# LAN9252-1.net
KiCad netlist of a schematic drawn in Altium Designer
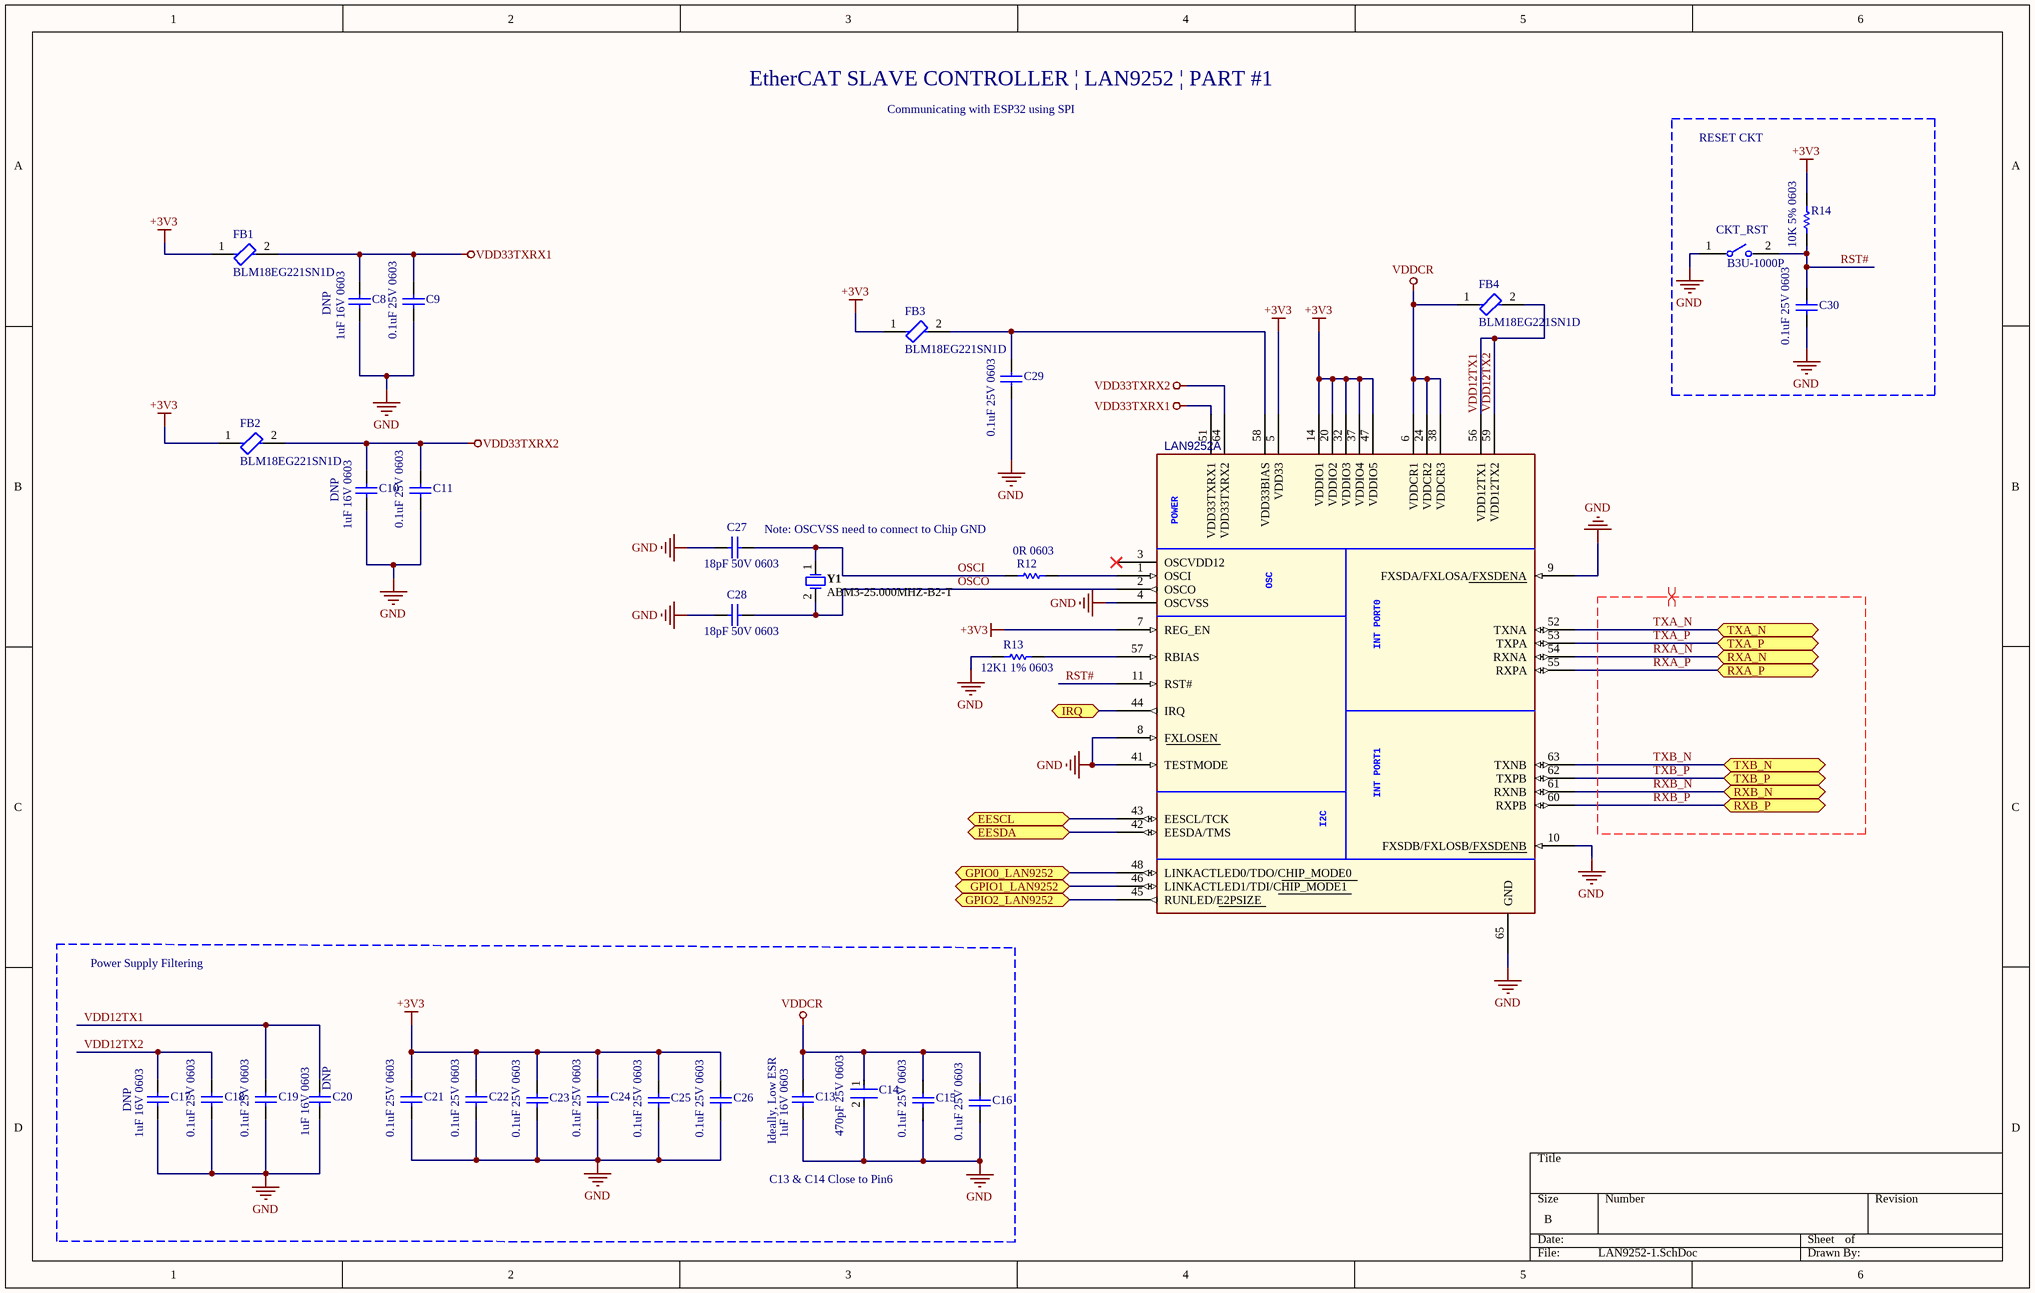
[diagram p0: LAN9252-1.SchDoc]

(export (version "E")
  (design (tool "Eeschema 10.0.6"))
  (components
    (comp (ref "C8")
      (value "1uF 16V 0603")
      (footprint "CAPC1608X90X35LL15T15")
      (fields (field (name "MANUFACTURER") "Kemet") (field (name "PART NUMBER") "C0603C105K4RACTU"))
      (libsource (lib "Altium Content Vault") (part "CAP"))
    )
    (comp (ref "C9")
      (value "0.1uF 25V 0603")
      (footprint "CAPC1608X90X35LL10T15")
      (fields (field (name "PART NUMBER") "GRM188R71E104KA01D") (field (name "MANUFACTURER") "Murata"))
      (libsource (lib "Altium Content Vault") (part "CAP"))
    )
    (comp (ref "C10")
      (value "1uF 16V 0603")
      (footprint "CAPC1608X90X35LL15T15")
      (fields (field (name "MANUFACTURER") "Kemet") (field (name "PART NUMBER") "C0603C105K4RACTU"))
      (libsource (lib "Altium Content Vault") (part "CAP"))
    )
    (comp (ref "C11")
      (value "0.1uF 25V 0603")
      (footprint "CAPC1608X90X35LL10T15")
      (fields (field (name "PART NUMBER") "GRM188R71E104KA01D") (field (name "MANUFACTURER") "Murata"))
      (libsource (lib "Altium Content Vault") (part "CAP"))
    )
    (comp (ref "C13")
      (value "1uF 16V 0603")
      (footprint "CAPC1608X90X35LL15T15")
      (fields (field (name "MANUFACTURER") "Kemet") (field (name "PART NUMBER") "C0603C105K4RACTU"))
      (libsource (lib "Altium Content Vault") (part "CAP"))
    )
    (comp (ref "C14")
      (value "470pF 25V 0603")
      (footprint "FP-C0603C-CF-MFG")
      (description "CAP CER 470PF 25V 10% X7R 0603")
      (fields (field (name "MANUFACTURER") "KEMET") (field (name "TOLERANCE") "0.1"))
      (libsource (lib "Altium Content Vault") (part "b4654b650e69147ec39a6b967a45e02"))
    )
    (comp (ref "C15")
      (value "0.1uF 25V 0603")
      (footprint "CAPC1608X90X35LL10T15")
      (fields (field (name "PART NUMBER") "GRM188R71E104KA01D") (field (name "MANUFACTURER") "Murata"))
      (libsource (lib "Altium Content Vault") (part "CAP"))
    )
    (comp (ref "C16")
      (value "0.1uF 25V 0603")
      (footprint "CAPC1608X90X35LL10T15")
      (fields (field (name "PART NUMBER") "GRM188R71E104KA01D") (field (name "MANUFACTURER") "Murata"))
      (libsource (lib "Altium Content Vault") (part "CAP"))
    )
    (comp (ref "C17")
      (value "1uF 16V 0603")
      (footprint "CAPC1608X90X35LL15T15")
      (fields (field (name "MANUFACTURER") "Kemet") (field (name "PART NUMBER") "C0603C105K4RACTU"))
      (libsource (lib "Altium Content Vault") (part "CAP"))
    )
    (comp (ref "C18")
      (value "0.1uF 25V 0603")
      (footprint "CAPC1608X90X35LL10T15")
      (fields (field (name "PART NUMBER") "GRM188R71E104KA01D") (field (name "MANUFACTURER") "Murata"))
      (libsource (lib "Altium Content Vault") (part "CAP"))
    )
    (comp (ref "C19")
      (value "0.1uF 25V 0603")
      (footprint "CAPC1608X90X35LL10T15")
      (fields (field (name "PART NUMBER") "GRM188R71E104KA01D") (field (name "MANUFACTURER") "Murata"))
      (libsource (lib "Altium Content Vault") (part "CAP"))
    )
    (comp (ref "C20")
      (value "1uF 16V 0603")
      (footprint "CAPC1608X90X35LL15T15")
      (fields (field (name "MANUFACTURER") "Kemet") (field (name "PART NUMBER") "C0603C105K4RACTU"))
      (libsource (lib "Altium Content Vault") (part "CAP"))
    )
    (comp (ref "C21")
      (value "0.1uF 25V 0603")
      (footprint "CAPC1608X90X35LL10T15")
      (fields (field (name "PART NUMBER") "GRM188R71E104KA01D") (field (name "MANUFACTURER") "Murata"))
      (libsource (lib "Altium Content Vault") (part "CAP"))
    )
    (comp (ref "C22")
      (value "0.1uF 25V 0603")
      (footprint "CAPC1608X90X35LL10T15")
      (fields (field (name "PART NUMBER") "GRM188R71E104KA01D") (field (name "MANUFACTURER") "Murata"))
      (libsource (lib "Altium Content Vault") (part "CAP"))
    )
    (comp (ref "C23")
      (value "0.1uF 25V 0603")
      (footprint "CAPC1608X90X35LL10T15")
      (fields (field (name "PART NUMBER") "GRM188R71E104KA01D") (field (name "MANUFACTURER") "Murata"))
      (libsource (lib "Altium Content Vault") (part "CAP"))
    )
    (comp (ref "C24")
      (value "0.1uF 25V 0603")
      (footprint "CAPC1608X90X35LL10T15")
      (fields (field (name "PART NUMBER") "GRM188R71E104KA01D") (field (name "MANUFACTURER") "Murata"))
      (libsource (lib "Altium Content Vault") (part "CAP"))
    )
    (comp (ref "C25")
      (value "0.1uF 25V 0603")
      (footprint "CAPC1608X90X35LL10T15")
      (fields (field (name "PART NUMBER") "GRM188R71E104KA01D") (field (name "MANUFACTURER") "Murata"))
      (libsource (lib "Altium Content Vault") (part "CAP"))
    )
    (comp (ref "C26")
      (value "0.1uF 25V 0603")
      (footprint "CAPC1608X90X35LL10T15")
      (fields (field (name "PART NUMBER") "GRM188R71E104KA01D") (field (name "MANUFACTURER") "Murata"))
      (libsource (lib "Altium Content Vault") (part "CAP"))
    )
    (comp (ref "C27")
      (value "18pF 50V 0603")
      (footprint "CAPC1608X90X40LL10T20")
      (description "Chip Capacitor, 18 pF, +/- 5%, 50 V, -55 to 125 degC, 0603 (1608 Metric), RoHS, Tape and Reel")
      (fields (field (name "TOLERANCE") "1%"))
      (libsource (lib "Altium Content Vault") (part "CAP-NP-2"))
    )
    (comp (ref "C28")
      (value "18pF 50V 0603")
      (footprint "CAPC1608X90X40LL10T20")
      (description "Chip Capacitor, 18 pF, +/- 5%, 50 V, -55 to 125 degC, 0603 (1608 Metric), RoHS, Tape and Reel")
      (fields (field (name "TOLERANCE") "1%"))
      (libsource (lib "Altium Content Vault") (part "CAP-NP-2"))
    )
    (comp (ref "C29")
      (value "0.1uF 25V 0603")
      (footprint "CAPC1608X90X35LL10T15")
      (fields (field (name "PART NUMBER") "GRM188R71E104KA01D") (field (name "MANUFACTURER") "Murata"))
      (libsource (lib "Altium Content Vault") (part "CAP"))
    )
    (comp (ref "C30")
      (value "0.1uF 25V 0603")
      (footprint "CAPC1608X90X35LL10T15")
      (fields (field (name "PART NUMBER") "GRM188R71E104KA01D") (field (name "MANUFACTURER") "Murata"))
      (libsource (lib "Altium Content Vault") (part "CAP"))
    )
    (comp (ref "CKT_RST")
      (value "B3U-1000P")
      (footprint "FP-B3U-1000P-MFG")
      (description "SWITCH TACTILE SPST-NO 0.05A 12V")
      (libsource (lib "Altium Content Vault") (part "ae622034201233ca1abcedc05908f33"))
    )
    (comp (ref "FB1")
      (value "BLM18EG221SN1D")
      (footprint "FP-BLM18-0_15-t0_8-MFG")
      (description "Chip Ferrite Bead, 0603, 220Ω @ 100MHz, 0.05Ω, 25%, 2A")
      (fields (field (name "TOLERANCE") "25%"))
      (libsource (lib "Altium Content Vault") (part "5f30dd21d616792df468990f7003faa"))
    )
    (comp (ref "FB2")
      (value "BLM18EG221SN1D")
      (footprint "FP-BLM18-0_15-t0_8-MFG")
      (description "Chip Ferrite Bead, 0603, 220Ω @ 100MHz, 0.05Ω, 25%, 2A")
      (fields (field (name "TOLERANCE") "25%"))
      (libsource (lib "Altium Content Vault") (part "5f30dd21d616792df468990f7003faa"))
    )
    (comp (ref "FB3")
      (value "BLM18EG221SN1D")
      (footprint "FP-BLM18-0_15-t0_8-MFG")
      (description "Chip Ferrite Bead, 0603, 220Ω @ 100MHz, 0.05Ω, 25%, 2A")
      (fields (field (name "TOLERANCE") "25%"))
      (libsource (lib "Altium Content Vault") (part "5f30dd21d616792df468990f7003faa"))
    )
    (comp (ref "FB4")
      (value "BLM18EG221SN1D")
      (footprint "FP-BLM18-0_15-t0_8-MFG")
      (description "Chip Ferrite Bead, 0603, 220Ω @ 100MHz, 0.05Ω, 25%, 2A")
      (fields (field (name "TOLERANCE") "25%"))
      (libsource (lib "Altium Content Vault") (part "5f30dd21d616792df468990f7003faa"))
    )
    (comp (ref "LAN9252")
      (value "~")
      (footprint "LAN9252_QFN")
      (description "IC, 2/3-Port EtherCAT® Slave Controller, QFN64")
      (fields (field (name "OWNER") "Manikandan"))
      (libsource (lib "UNG_UNG") (part "LAN9252_QFN64"))
    )
    (comp (ref "R12")
      (value "0R 0603")
      (footprint "RESC1608X55X25ML10T15")
      (description "Chip Resistor, 0 Ohm, +/- 5%, 0.1 W, -55 to 155 degC, 0603 (1608 Metric), RoHS, Tape and Reel")
      (fields (field (name "TOLERANCE") "5%") (field (name "MANUFACTURER") "Yageo"))
      (libsource (lib "Altium Content Vault") (part "RES-2"))
    )
    (comp (ref "R13")
      (value "12K1 1% 0603")
      (footprint "RESC0603X28X15ML05T05")
      (fields (field (name "PART NUMBER") "CRCW020112K1FNED") (field (name "MANUFACTURER") "Vishay Dale"))
      (libsource (lib "Altium Content Vault") (part "RES"))
    )
    (comp (ref "R14")
      (value "10K 5% 0603")
      (footprint "RESC1608X55X25ML10T15")
      (description "Chip Resistor, 10 KOhm, +/- 1%, 01 W, -55 to 155 degC, 0603 (1608 Metric), RoHS, Tape and Reel")
      (fields (field (name "MANUFACTURER") "Yageo") (field (name "TOLERANCE") "1%"))
      (libsource (lib "Altium Content Vault") (part "RES-2"))
    )
    (comp (ref "Y1")
      (value "ABM3-25.000MHZ-B2-T")
      (footprint "ABRA-ABM3_V")
      (description "Miniature Ceramic Crystal, 25 MHz, +/- 20 ppm, -20 to 70 degC, 2-Pin SMD, RoHS, Tape and Reel")
      (fields (field (name "TOLERANCE") "20PPM") (field (name "MANUFACTURER") "ABRACON"))
      (libsource (lib "Altium Content Vault") (part "XTAL-1-2-2"))
    )
  )
  (nets
    (net (code "1") (name "+3V3") (class "Default")
      (node (ref "C21") (pin "2") (pinfunction "2_2") (pintype "passive"))
      (node (ref "C22") (pin "2") (pinfunction "2_2") (pintype "passive"))
      (node (ref "C23") (pin "2") (pinfunction "2_2") (pintype "passive"))
      (node (ref "C24") (pin "2") (pinfunction "2_2") (pintype "passive"))
      (node (ref "C25") (pin "2") (pinfunction "2_2") (pintype "passive"))
      (node (ref "C26") (pin "2") (pinfunction "2_2") (pintype "passive"))
      (node (ref "FB1") (pin "1") (pinfunction "1_1") (pintype "passive"))
      (node (ref "FB2") (pin "1") (pinfunction "1_1") (pintype "passive"))
      (node (ref "FB3") (pin "1") (pinfunction "1_1") (pintype "passive"))
      (node (ref "LAN9252") (pin "14") (pinfunction "VDDIO1_14") (pintype "power_in"))
      (node (ref "LAN9252") (pin "20") (pinfunction "VDDIO2_20") (pintype "power_in"))
      (node (ref "LAN9252") (pin "32") (pinfunction "VDDIO3_32") (pintype "power_in"))
      (node (ref "LAN9252") (pin "37") (pinfunction "VDDIO4_37") (pintype "power_in"))
      (node (ref "LAN9252") (pin "47") (pinfunction "VDDIO5_47") (pintype "power_in"))
      (node (ref "LAN9252") (pin "5") (pinfunction "VDD33_5") (pintype "power_in"))
      (node (ref "LAN9252") (pin "7") (pinfunction "REG_EN_7") (pintype "input"))
      (node (ref "R14") (pin "2") (pinfunction "2_2") (pintype "passive"))
    )
    (net (code "2") (name "/EESCL") (class "Default")
      (node (ref "LAN9252") (pin "43") (pinfunction "EESCL/TCK_43") (pintype "bidirectional"))
    )
    (net (code "3") (name "/EESDA") (class "Default")
      (node (ref "LAN9252") (pin "42") (pinfunction "EESDA/TMS_42") (pintype "bidirectional"))
    )
    (net (code "4") (name "/GPIO0_LAN9252") (class "Default")
      (node (ref "LAN9252") (pin "48") (pinfunction "LINKACTLED0/TDO/CHIP_MODE0_48") (pintype "bidirectional"))
    )
    (net (code "5") (name "/GPIO1_LAN9252") (class "Default")
      (node (ref "LAN9252") (pin "46") (pinfunction "LINKACTLED1/TDI/CHIP_MODE1_46") (pintype "bidirectional"))
    )
    (net (code "6") (name "/GPIO2_LAN9252") (class "Default")
      (node (ref "LAN9252") (pin "45") (pinfunction "RUNLED/E2PSIZE_45") (pintype "output"))
    )
    (net (code "7") (name "/IRQ") (class "Default")
      (node (ref "LAN9252") (pin "44") (pinfunction "IRQ_44") (pintype "output"))
    )
    (net (code "8") (name "/OSCI") (class "Default")
      (node (ref "C27") (pin "2") (pinfunction "2_2") (pintype "passive"))
      (node (ref "R12") (pin "1") (pinfunction "1_1") (pintype "passive"))
      (node (ref "Y1") (pin "1") (pinfunction "1_1") (pintype "passive"))
    )
    (net (code "9") (name "/OSCO") (class "Default")
      (node (ref "C28") (pin "2") (pinfunction "2_2") (pintype "passive"))
      (node (ref "LAN9252") (pin "2") (pinfunction "OSCO_2") (pintype "output"))
      (node (ref "Y1") (pin "2") (pinfunction "2_2") (pintype "passive"))
    )
    (net (code "10") (name "/RST#") (class "Default")
      (node (ref "C30") (pin "2") (pinfunction "2_2") (pintype "passive"))
      (node (ref "CKT_RST") (pin "2") (pinfunction "2_2") (pintype "passive"))
      (node (ref "LAN9252") (pin "11") (pinfunction "RST#_11") (pintype "input"))
      (node (ref "R14") (pin "1") (pinfunction "1_1") (pintype "passive"))
    )
    (net (code "11") (name "/RXA_N") (class "Default")
      (node (ref "LAN9252") (pin "54") (pinfunction "RXNA_54") (pintype "bidirectional"))
    )
    (net (code "12") (name "/RXA_P") (class "Default")
      (node (ref "LAN9252") (pin "55") (pinfunction "RXPA_55") (pintype "bidirectional"))
    )
    (net (code "13") (name "/RXB_N") (class "Default")
      (node (ref "LAN9252") (pin "61") (pinfunction "RXNB_61") (pintype "bidirectional"))
    )
    (net (code "14") (name "/RXB_P") (class "Default")
      (node (ref "LAN9252") (pin "60") (pinfunction "RXPB_60") (pintype "bidirectional"))
    )
    (net (code "15") (name "/TXA_N") (class "Default")
      (node (ref "LAN9252") (pin "52") (pinfunction "TXNA_52") (pintype "bidirectional"))
    )
    (net (code "16") (name "/TXA_P") (class "Default")
      (node (ref "LAN9252") (pin "53") (pinfunction "TXPA_53") (pintype "bidirectional"))
    )
    (net (code "17") (name "/TXB_N") (class "Default")
      (node (ref "LAN9252") (pin "63") (pinfunction "TXNB_63") (pintype "bidirectional"))
    )
    (net (code "18") (name "/TXB_P") (class "Default")
      (node (ref "LAN9252") (pin "62") (pinfunction "TXPB_62") (pintype "bidirectional"))
    )
    (net (code "19") (name "/VDD12TX1") (class "Default")
      (node (ref "C17") (pin "2") (pinfunction "2_2") (pintype "passive"))
      (node (ref "C18") (pin "2") (pinfunction "2_2") (pintype "passive"))
      (node (ref "C19") (pin "2") (pinfunction "2_2") (pintype "passive"))
      (node (ref "C20") (pin "2") (pinfunction "2_2") (pintype "passive"))
      (node (ref "FB4") (pin "2") (pinfunction "2_2") (pintype "passive"))
      (node (ref "LAN9252") (pin "56") (pinfunction "VDD12TX1_56") (pintype "power_in"))
      (node (ref "LAN9252") (pin "59") (pinfunction "VDD12TX2_59") (pintype "power_in"))
    )
    (net (code "20") (name "GND") (class "Default")
      (node (ref "C10") (pin "1") (pinfunction "1_1") (pintype "passive"))
      (node (ref "C11") (pin "1") (pinfunction "1_1") (pintype "passive"))
      (node (ref "C13") (pin "1") (pinfunction "1_1") (pintype "passive"))
      (node (ref "C14") (pin "2") (pinfunction "2_2") (pintype "passive"))
      (node (ref "C15") (pin "1") (pinfunction "1_1") (pintype "passive"))
      (node (ref "C16") (pin "1") (pinfunction "1_1") (pintype "passive"))
      (node (ref "C17") (pin "1") (pinfunction "1_1") (pintype "passive"))
      (node (ref "C18") (pin "1") (pinfunction "1_1") (pintype "passive"))
      (node (ref "C19") (pin "1") (pinfunction "1_1") (pintype "passive"))
      (node (ref "C20") (pin "1") (pinfunction "1_1") (pintype "passive"))
      (node (ref "C21") (pin "1") (pinfunction "1_1") (pintype "passive"))
      (node (ref "C22") (pin "1") (pinfunction "1_1") (pintype "passive"))
      (node (ref "C23") (pin "1") (pinfunction "1_1") (pintype "passive"))
      (node (ref "C24") (pin "1") (pinfunction "1_1") (pintype "passive"))
      (node (ref "C25") (pin "1") (pinfunction "1_1") (pintype "passive"))
      (node (ref "C26") (pin "1") (pinfunction "1_1") (pintype "passive"))
      (node (ref "C27") (pin "1") (pinfunction "1_1") (pintype "passive"))
      (node (ref "C28") (pin "1") (pinfunction "1_1") (pintype "passive"))
      (node (ref "C29") (pin "1") (pinfunction "1_1") (pintype "passive"))
      (node (ref "C30") (pin "1") (pinfunction "1_1") (pintype "passive"))
      (node (ref "C8") (pin "1") (pinfunction "1_1") (pintype "passive"))
      (node (ref "C9") (pin "1") (pinfunction "1_1") (pintype "passive"))
      (node (ref "CKT_RST") (pin "1") (pinfunction "1_1") (pintype "passive"))
      (node (ref "LAN9252") (pin "10") (pinfunction "FXSDB/FXLOSB/FXSDENB_10") (pintype "input"))
      (node (ref "LAN9252") (pin "4") (pinfunction "OSCVSS_4") (pintype "power_in"))
      (node (ref "LAN9252") (pin "41") (pinfunction "TESTMODE_41") (pintype "input"))
      (node (ref "LAN9252") (pin "65") (pinfunction "GND_65") (pintype "power_in"))
      (node (ref "LAN9252") (pin "8") (pinfunction "FXLOSEN_8") (pintype "input"))
      (node (ref "LAN9252") (pin "9") (pinfunction "FXSDA/FXLOSA/FXSDENA_9") (pintype "input"))
      (node (ref "R13") (pin "1") (pinfunction "1_1") (pintype "passive"))
    )
    (net (code "21") (name "Net-(LAN9252A-OSCI)") (class "Default")
      (node (ref "LAN9252") (pin "1") (pinfunction "OSCI_1") (pintype "input"))
      (node (ref "R12") (pin "2") (pinfunction "2_2") (pintype "passive"))
    )
    (net (code "22") (name "Net-(LAN9252A-RBIAS)") (class "Default")
      (node (ref "LAN9252") (pin "57") (pinfunction "RBIAS_57") (pintype "input"))
      (node (ref "R13") (pin "2") (pinfunction "2_2") (pintype "passive"))
    )
    (net (code "23") (name "Net-(LAN9252A-VDD33BIAS)") (class "Default")
      (node (ref "C29") (pin "2") (pinfunction "2_2") (pintype "passive"))
      (node (ref "FB3") (pin "2") (pinfunction "2_2") (pintype "passive"))
      (node (ref "LAN9252") (pin "58") (pinfunction "VDD33BIAS_58") (pintype "power_in"))
    )
    (net (code "24") (name "VDD33TXRX1") (class "Default")
      (node (ref "C8") (pin "2") (pinfunction "2_2") (pintype "passive"))
      (node (ref "C9") (pin "2") (pinfunction "2_2") (pintype "passive"))
      (node (ref "FB1") (pin "2") (pinfunction "2_2") (pintype "passive"))
      (node (ref "LAN9252") (pin "51") (pinfunction "VDD33TXRX1_51") (pintype "power_in"))
    )
    (net (code "25") (name "VDD33TXRX2") (class "Default")
      (node (ref "C10") (pin "2") (pinfunction "2_2") (pintype "passive"))
      (node (ref "C11") (pin "2") (pinfunction "2_2") (pintype "passive"))
      (node (ref "FB2") (pin "2") (pinfunction "2_2") (pintype "passive"))
      (node (ref "LAN9252") (pin "64") (pinfunction "VDD33TXRX2_64") (pintype "power_in"))
    )
    (net (code "26") (name "VDDCR") (class "Default")
      (node (ref "C13") (pin "2") (pinfunction "2_2") (pintype "passive"))
      (node (ref "C14") (pin "1") (pinfunction "1_1") (pintype "passive"))
      (node (ref "C15") (pin "2") (pinfunction "2_2") (pintype "passive"))
      (node (ref "C16") (pin "2") (pinfunction "2_2") (pintype "passive"))
      (node (ref "FB4") (pin "1") (pinfunction "1_1") (pintype "passive"))
      (node (ref "LAN9252") (pin "24") (pinfunction "VDDCR2_24") (pintype "power_in"))
      (node (ref "LAN9252") (pin "38") (pinfunction "VDDCR3_38") (pintype "power_in"))
      (node (ref "LAN9252") (pin "6") (pinfunction "VDDCR1_6") (pintype "power_in"))
    )
    (net (code "27") (name "unconnected-(LAN9252A-OSCVDD12-Pad3)") (class "Default")
      (node (ref "LAN9252") (pin "3") (pinfunction "OSCVDD12_3") (pintype "power_in+no_connect"))
    )
  )
)
